# RS485.net
KiCad netlist of a schematic drawn in Altium Designer
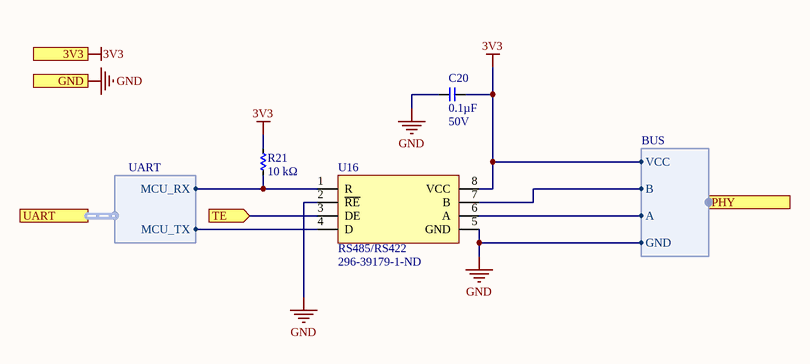
[diagram p0: RS485.SchDoc]

(export (version "E")
  (design (tool "Eeschema 10.0.6"))
  (components
    (comp (ref "C20")
      (value "__template_cap")
      (footprint "C0603")
      (description "CAP CER 0603 0.1µF X7R 50V 10%")
      (fields
        (field (name "CAPACITANCE (SHORTHAND)") "0.1µF")
        (field (name "MANUFACTURER") "Murata Electronics North America")
        (field (name "RATED VOLTAGE") "50V")
      )
      (libsource (lib "passives") (part "__template_cap"))
    )
    (comp (ref "R21")
      (value "__template_resistor")
      (footprint "R0603")
      (description "RES SMD 10K OHM 1% 1/10W 0603")
      (fields
        (field (name "MANUFACTURER PART NUMBER") "RC0603FR-0710KL")
        (field (name "MANUFACTURER") "Yageo")
        (field (name "RESISTANCE") "10 kΩ")
      )
      (libsource (lib "passives") (part "__template_resistor"))
    )
    (comp (ref "U16")
      (value "RS485/RS422")
      (footprint "8SOIC150")
      (fields
        (field (name "MANUFACTURER") "Texas Instruments")
        (field (name "MANUFACTURER PART NUMBER") "SN65HVD72DGKR")
        (field (name "SUPPLIER PART NUMBER 1") "296-39179-1-ND")
      )
      (libsource (lib "SSI") (part "SN65HVD7x"))
    )
  )
  (nets
    (net (code "3") (name "/A") (class "Default")
      (node (ref "U16") (pin "6") (pinfunction "A_6") (pintype "passive"))
    )
    (net (code "4") (name "/B") (class "Default")
      (node (ref "U16") (pin "7") (pinfunction "B_7") (pintype "passive"))
    )
    (net (code "5") (name "/MCU_RX") (class "Default")
      (node (ref "R21") (pin "2") (pintype "passive"))
      (node (ref "U16") (pin "1") (pinfunction "R_1") (pintype "passive"))
    )
    (net (code "6") (name "/MCU_TX") (class "Default")
      (node (ref "U16") (pin "4") (pinfunction "D_4") (pintype "passive"))
    )
    (net (code "7") (name "/TE") (class "Default")
      (node (ref "U16") (pin "3") (pinfunction "DE_3") (pintype "passive"))
    )
    (net (code "10") (name "3V3") (class "Default")
      (node (ref "C20") (pin "2") (pintype "passive"))
      (node (ref "R21") (pin "1") (pintype "passive"))
      (node (ref "U16") (pin "8") (pinfunction "VCC_8") (pintype "passive"))
    )
    (net (code "11") (name "GND") (class "Default")
      (node (ref "C20") (pin "1") (pintype "passive"))
      (node (ref "U16") (pin "2") (pinfunction "~{RE}_2") (pintype "passive"))
      (node (ref "U16") (pin "5") (pinfunction "GND_5") (pintype "passive"))
    )
  )
)
